# praline.net
KiCad netlist of a schematic drawn in Altium Designer
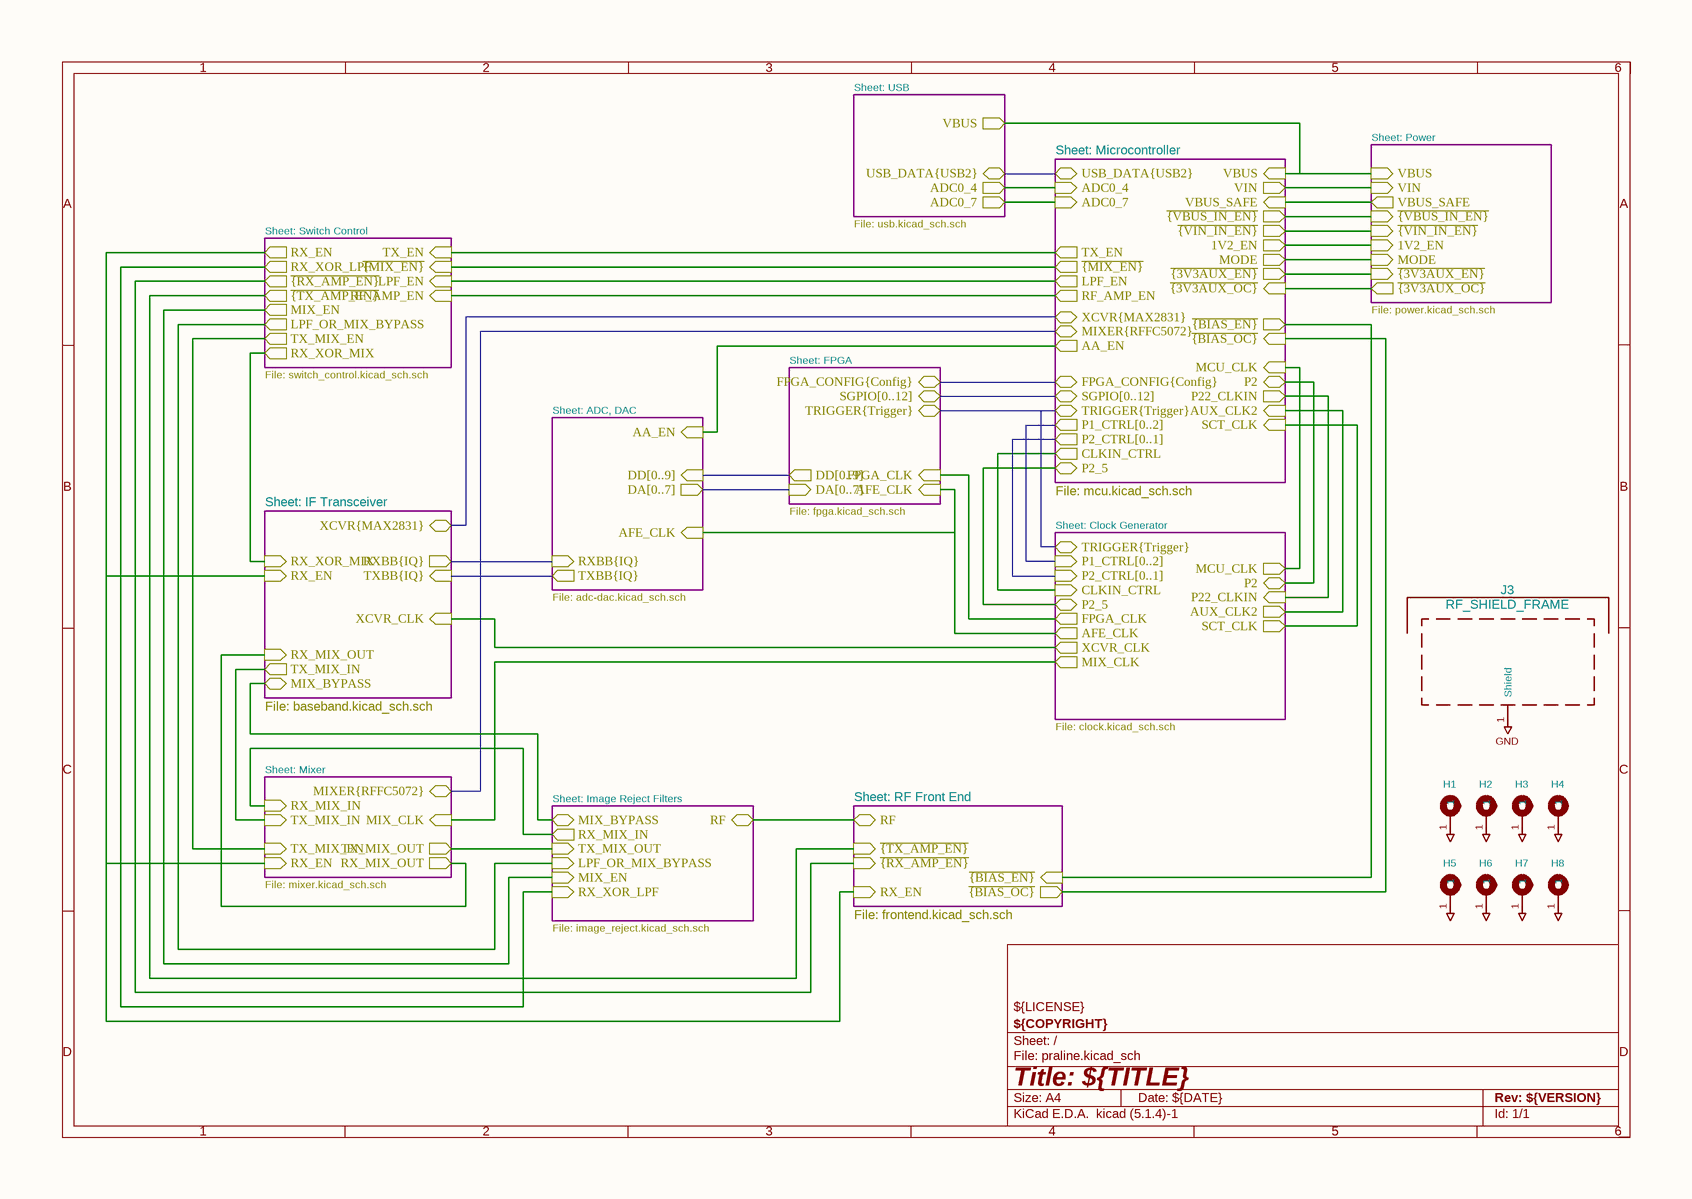
[diagram p0: praline.SchDoc]

(export (version "E")
  (design (tool "Eeschema 10.0.6"))
  (components
    (comp (ref "H1")
      (value "MountingHole_Pad")
      (footprint "MountingHole_3.2mm_M3_Pad_Via")
      (description "Mounting Hole with connection")
      (libsource (lib "Mechanical") (part "MountingHole_Pad"))
    )
    (comp (ref "H2")
      (value "MountingHole_Pad")
      (footprint "MountingHole_3.2mm_M3_Pad_Via")
      (description "Mounting Hole with connection")
      (libsource (lib "Mechanical") (part "MountingHole_Pad"))
    )
    (comp (ref "H3")
      (value "MountingHole_Pad")
      (footprint "MountingHole_3.2mm_M3_Pad_Via")
      (description "Mounting Hole with connection")
      (libsource (lib "Mechanical") (part "MountingHole_Pad"))
    )
    (comp (ref "H4")
      (value "MountingHole_Pad")
      (footprint "MountingHole_3.2mm_M3_Pad_Via")
      (description "Mounting Hole with connection")
      (libsource (lib "Mechanical") (part "MountingHole_Pad"))
    )
    (comp (ref "H5")
      (value "MountingHole_Pad")
      (footprint "MountingHole_2.2mm_M2_Pad_Via")
      (description "Mounting Hole with connection")
      (libsource (lib "Mechanical") (part "MountingHole_Pad"))
    )
    (comp (ref "H6")
      (value "MountingHole_Pad")
      (footprint "MountingHole_2.2mm_M2_Pad_Via")
      (description "Mounting Hole with connection")
      (libsource (lib "Mechanical") (part "MountingHole_Pad"))
    )
    (comp (ref "H7")
      (value "MountingHole_Pad")
      (footprint "MountingHole_2.2mm_M2_Pad_Via")
      (description "Mounting Hole with connection")
      (libsource (lib "Mechanical") (part "MountingHole_Pad"))
    )
    (comp (ref "H8")
      (value "MountingHole_Pad")
      (footprint "MountingHole_2.2mm_M2_Pad_Via")
      (description "Mounting Hole with connection")
      (libsource (lib "Mechanical") (part "MountingHole_Pad"))
    )
    (comp (ref "J3")
      (value "RF_SHIELD_FRAME")
      (footprint "Laird_Technologies_BMI-S-230-F_50.8x38.1mm")
      (description "BOARD SHIELD 2INX1.5IN FRAME")
      (fields (field (name "MANUFACTURER") "TE Connectivity") (field (name "PART NUMBER") "2118732-2"))
      (libsource (lib "Device") (part "RFShield_TwoPieces"))
    )
  )
  (nets
    (net (code "56") (name "GND") (class "Default")
      (node (ref "H1") (pin "1") (pinfunction "1_1") (pintype "passive"))
      (node (ref "H2") (pin "1") (pinfunction "1_1") (pintype "passive"))
      (node (ref "H3") (pin "1") (pinfunction "1_1") (pintype "passive"))
      (node (ref "H4") (pin "1") (pinfunction "1_1") (pintype "passive"))
      (node (ref "H5") (pin "1") (pinfunction "1_1") (pintype "passive"))
      (node (ref "H6") (pin "1") (pinfunction "1_1") (pintype "passive"))
      (node (ref "H7") (pin "1") (pinfunction "1_1") (pintype "passive"))
      (node (ref "H8") (pin "1") (pinfunction "1_1") (pintype "passive"))
      (node (ref "J3") (pin "1") (pinfunction "Shield_1") (pintype "passive"))
    )
  )
)
